# scanner.net
KiCad netlist of a schematic drawn in EAGLE
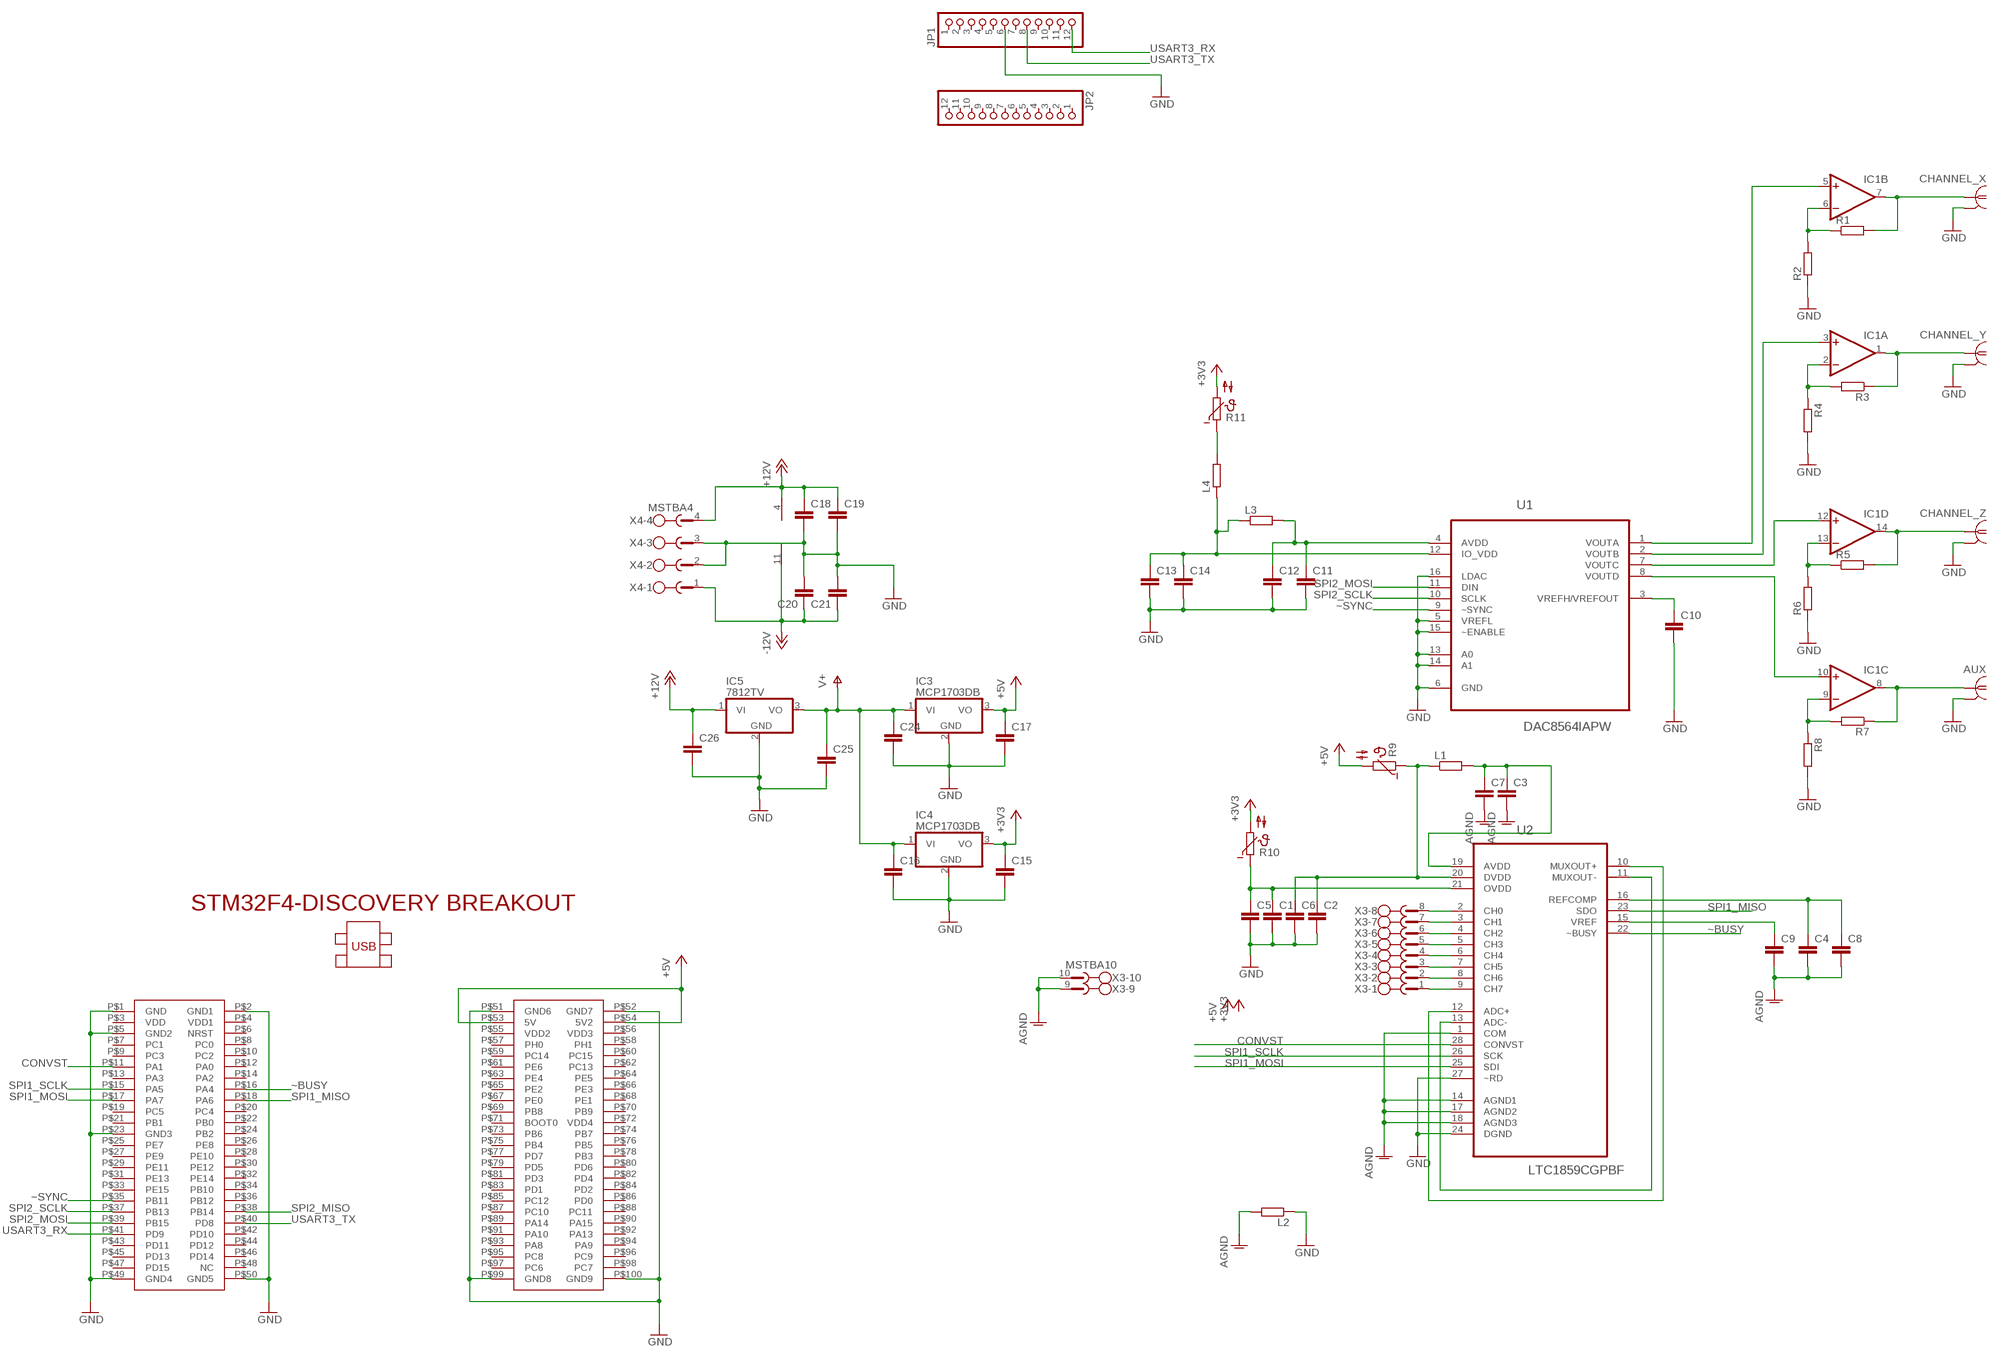
[diagram p0: schematic, sheet 1]

(export (version "E")
  (design (tool "Eeschema 10.0.6"))
  (components
    (comp (ref "AUX")
      (value "1-227161-0")
      (footprint "eagle-import:AMP_227161")
      (fields (field (name "MF") "TYCO ELECTRONICS") (field (name "MPN") "1-227161"))
      (libsource (lib "eagle-import") (part "?2271611--0"))
    )
    (comp (ref "C1")
      (value "C-EUC0805")
      (footprint "eagle-import:C0805")
      (libsource (lib "eagle-import") (part "C-EUC0805"))
    )
    (comp (ref "C2")
      (value "C-EUC0805")
      (footprint "eagle-import:C0805")
      (libsource (lib "eagle-import") (part "C-EUC0805"))
    )
    (comp (ref "C3")
      (value "C-EUC0805")
      (footprint "eagle-import:C0805")
      (libsource (lib "eagle-import") (part "C-EUC0805"))
    )
    (comp (ref "C4")
      (value "C-EUC0805")
      (footprint "eagle-import:C0805")
      (libsource (lib "eagle-import") (part "C-EUC0805"))
    )
    (comp (ref "C5")
      (value "C-EUC1206")
      (footprint "eagle-import:C1206")
      (libsource (lib "eagle-import") (part "C-EUC1206"))
    )
    (comp (ref "C6")
      (value "C-EUC1206")
      (footprint "eagle-import:C1206")
      (libsource (lib "eagle-import") (part "C-EUC1206"))
    )
    (comp (ref "C7")
      (value "C-EUC1206")
      (footprint "eagle-import:C1206")
      (libsource (lib "eagle-import") (part "C-EUC1206"))
    )
    (comp (ref "C8")
      (value "C-EUC1206")
      (footprint "eagle-import:C1206")
      (libsource (lib "eagle-import") (part "C-EUC1206"))
    )
    (comp (ref "C9")
      (value "C-EUC1206")
      (footprint "eagle-import:C1206")
      (libsource (lib "eagle-import") (part "C-EUC1206"))
    )
    (comp (ref "C10")
      (value "C-EUC0805")
      (footprint "eagle-import:C0805")
      (libsource (lib "eagle-import") (part "C-EUC0805"))
    )
    (comp (ref "C11")
      (value "C-EUC0805")
      (footprint "eagle-import:C0805")
      (libsource (lib "eagle-import") (part "C-EUC0805"))
    )
    (comp (ref "C12")
      (value "C-EUC1206")
      (footprint "eagle-import:C1206")
      (libsource (lib "eagle-import") (part "C-EUC1206"))
    )
    (comp (ref "C13")
      (value "C-EUC1206")
      (footprint "eagle-import:C1206")
      (libsource (lib "eagle-import") (part "C-EUC1206"))
    )
    (comp (ref "C14")
      (value "C-EUC0805")
      (footprint "eagle-import:C0805")
      (libsource (lib "eagle-import") (part "C-EUC0805"))
    )
    (comp (ref "C15")
      (value "C-EUC0805")
      (footprint "eagle-import:C0805")
      (libsource (lib "eagle-import") (part "C-EUC0805"))
    )
    (comp (ref "C16")
      (value "C-EUC0805")
      (footprint "eagle-import:C0805")
      (libsource (lib "eagle-import") (part "C-EUC0805"))
    )
    (comp (ref "C17")
      (value "C-EUC0805")
      (footprint "eagle-import:C0805")
      (libsource (lib "eagle-import") (part "C-EUC0805"))
    )
    (comp (ref "C18")
      (value "C-EUC1206")
      (footprint "eagle-import:C1206")
      (libsource (lib "eagle-import") (part "C-EUC1206"))
    )
    (comp (ref "C19")
      (value "C-EUC0805")
      (footprint "eagle-import:C0805")
      (libsource (lib "eagle-import") (part "C-EUC0805"))
    )
    (comp (ref "C20")
      (value "C-EUC1206")
      (footprint "eagle-import:C1206")
      (libsource (lib "eagle-import") (part "C-EUC1206"))
    )
    (comp (ref "C21")
      (value "C-EUC0805")
      (footprint "eagle-import:C0805")
      (libsource (lib "eagle-import") (part "C-EUC0805"))
    )
    (comp (ref "C24")
      (value "C-EUC0805")
      (footprint "eagle-import:C0805")
      (libsource (lib "eagle-import") (part "C-EUC0805"))
    )
    (comp (ref "C25")
      (value "C-EUC1206")
      (footprint "eagle-import:C1206")
      (libsource (lib "eagle-import") (part "C-EUC1206"))
    )
    (comp (ref "C26")
      (value "C-EUC1206")
      (footprint "eagle-import:C1206")
      (libsource (lib "eagle-import") (part "C-EUC1206"))
    )
    (comp (ref "CHANNEL_X")
      (value "1-227161-0")
      (footprint "eagle-import:AMP_227161")
      (fields (field (name "MF") "TYCO ELECTRONICS") (field (name "MPN") "1-227161"))
      (libsource (lib "eagle-import") (part "?2271611--0"))
    )
    (comp (ref "CHANNEL_Y")
      (value "1-227161-0")
      (footprint "eagle-import:AMP_227161")
      (fields (field (name "MF") "TYCO ELECTRONICS") (field (name "MPN") "1-227161"))
      (libsource (lib "eagle-import") (part "?2271611--0"))
    )
    (comp (ref "CHANNEL_Z")
      (value "1-227161-0")
      (footprint "eagle-import:AMP_227161")
      (fields (field (name "MF") "TYCO ELECTRONICS") (field (name "MPN") "1-227161"))
      (libsource (lib "eagle-import") (part "?2271611--0"))
    )
    (comp (ref "IC1")
      (value "4AMP_P4+11D")
      (footprint "eagle-import:SO14")
      (libsource (lib "eagle-import") (part "4AMP_P4+11D"))
    )
    (comp (ref "IC3")
      (value "MCP1703DB")
      (footprint "eagle-import:SOT223")
      (libsource (lib "eagle-import") (part "MCP1703DB"))
    )
    (comp (ref "IC4")
      (value "MCP1703DB")
      (footprint "eagle-import:SOT223")
      (libsource (lib "eagle-import") (part "MCP1703DB"))
    )
    (comp (ref "IC5")
      (value "7812TV")
      (footprint "eagle-import:TO220V")
      (libsource (lib "eagle-import") (part "78TV12"))
    )
    (comp (ref "JP1")
      (value "PINHD-1X12")
      (footprint "eagle-import:1X12")
      (libsource (lib "eagle-import") (part "PINHD-1X12"))
    )
    (comp (ref "JP2")
      (value "PINHD-1X12")
      (footprint "eagle-import:1X12")
      (libsource (lib "eagle-import") (part "PINHD-1X12"))
    )
    (comp (ref "L1")
      (value "R-EU_M1206")
      (footprint "eagle-import:M1206")
      (libsource (lib "eagle-import") (part "R-EU_M1206"))
    )
    (comp (ref "L2")
      (value "R-EU_M1206")
      (footprint "eagle-import:M1206")
      (libsource (lib "eagle-import") (part "R-EU_M1206"))
    )
    (comp (ref "L3")
      (value "R-EU_M1206")
      (footprint "eagle-import:M1206")
      (libsource (lib "eagle-import") (part "R-EU_M1206"))
    )
    (comp (ref "L4")
      (value "R-EU_M1206")
      (footprint "eagle-import:M1206")
      (libsource (lib "eagle-import") (part "R-EU_M1206"))
    )
    (comp (ref "R1")
      (value "R-EU_M0805")
      (footprint "eagle-import:M0805")
      (libsource (lib "eagle-import") (part "R-EU_M0805"))
    )
    (comp (ref "R2")
      (value "R-EU_M0805")
      (footprint "eagle-import:M0805")
      (libsource (lib "eagle-import") (part "R-EU_M0805"))
    )
    (comp (ref "R3")
      (value "R-EU_M0805")
      (footprint "eagle-import:M0805")
      (libsource (lib "eagle-import") (part "R-EU_M0805"))
    )
    (comp (ref "R4")
      (value "R-EU_M0805")
      (footprint "eagle-import:M0805")
      (libsource (lib "eagle-import") (part "R-EU_M0805"))
    )
    (comp (ref "R5")
      (value "R-EU_M0805")
      (footprint "eagle-import:M0805")
      (libsource (lib "eagle-import") (part "R-EU_M0805"))
    )
    (comp (ref "R6")
      (value "R-EU_M0805")
      (footprint "eagle-import:M0805")
      (libsource (lib "eagle-import") (part "R-EU_M0805"))
    )
    (comp (ref "R7")
      (value "R-EU_M0805")
      (footprint "eagle-import:M0805")
      (libsource (lib "eagle-import") (part "R-EU_M0805"))
    )
    (comp (ref "R8")
      (value "R-EU_M0805")
      (footprint "eagle-import:M0805")
      (libsource (lib "eagle-import") (part "R-EU_M0805"))
    )
    (comp (ref "R9")
      (value "NTC644C")
      (footprint "eagle-import:N644C")
      (libsource (lib "eagle-import") (part "NTC644C"))
    )
    (comp (ref "R10")
      (value "NTC644C")
      (footprint "eagle-import:N644C")
      (libsource (lib "eagle-import") (part "NTC644C"))
    )
    (comp (ref "R11")
      (value "NTC644C")
      (footprint "eagle-import:N644C")
      (libsource (lib "eagle-import") (part "NTC644C"))
    )
    (comp (ref "U$2")
      (value "STM32F4-DISCOVERY")
      (footprint "eagle-import:STM32F4-DISCOVERY")
      (libsource (lib "eagle-import") (part "STM32F4-DISCOVERY"))
    )
    (comp (ref "U1")
      (value "DAC8564IAPW")
      (footprint "eagle-import:SOP65P640X120-16N")
      (libsource (lib "eagle-import") (part "DAC8564IAPW"))
    )
    (comp (ref "U2")
      (value "LTC1859CGPBF")
      (footprint "eagle-import:SOP65P780X200-28N")
      (fields (field (name "MPN") "LTC1859CG#PBF"))
      (libsource (lib "eagle-import") (part "LTC1859CGPBF"))
    )
    (comp (ref "X3")
      (value "MSTBA10")
      (footprint "eagle-import:MSTBA10")
      (fields (field (name "MF") "FARNELL") (field (name "MPN") "1757323"))
      (libsource (lib "eagle-import") (part "MSTBA10"))
    )
    (comp (ref "X4")
      (value "MSTBA4")
      (footprint "eagle-import:MSTBA4")
      (fields (field (name "MF") "FARNELL") (field (name "MPN") "1757268"))
      (libsource (lib "eagle-import") (part "MSTBA4"))
    )
  )
  (nets
    (net (code "1") (name "+3V3") (class "Default")
      (node (ref "C15") (pin "1") (pinfunction "1_1") (pintype "passive"))
      (node (ref "IC4") (pin "3") (pinfunction "VO_3") (pintype "passive"))
      (node (ref "R10") (pin "2") (pinfunction "2_2") (pintype "passive"))
      (node (ref "R11") (pin "2") (pinfunction "2_2") (pintype "passive"))
    )
    (net (code "2") (name "+5V") (class "Default")
      (node (ref "C17") (pin "1") (pinfunction "1_1") (pintype "passive"))
      (node (ref "IC3") (pin "3") (pinfunction "VO_3") (pintype "passive"))
      (node (ref "R9") (pin "2") (pinfunction "2_2") (pintype "passive"))
      (node (ref "U$2") (pin "P$53") (pinfunction "5V_P$53") (pintype "bidirectional"))
      (node (ref "U$2") (pin "P$54") (pinfunction "5V2_P$54") (pintype "bidirectional"))
    )
    (net (code "3") (name "+12V") (class "Default")
      (node (ref "C18") (pin "1") (pinfunction "1_1") (pintype "passive"))
      (node (ref "C19") (pin "1") (pinfunction "1_1") (pintype "passive"))
      (node (ref "C26") (pin "1") (pinfunction "1_1") (pintype "passive"))
      (node (ref "IC1") (pin "4") (pinfunction "V+_4") (pintype "power_in"))
      (node (ref "IC5") (pin "1") (pinfunction "VI_1") (pintype "input"))
      (node (ref "X4") (pin "4") (pinfunction "1_4") (pintype "passive"))
    )
    (net (code "4") (name "-12V") (class "Default")
      (node (ref "C20") (pin "1") (pinfunction "1_1") (pintype "passive"))
      (node (ref "C21") (pin "1") (pinfunction "1_1") (pintype "passive"))
      (node (ref "IC1") (pin "11") (pinfunction "V-_11") (pintype "power_in"))
      (node (ref "X4") (pin "1") (pinfunction "1_1") (pintype "passive"))
    )
    (net (code "5") (name "/CONVST") (class "Default")
      (node (ref "U$2") (pin "P$11") (pinfunction "PA1_P$11") (pintype "bidirectional"))
      (node (ref "U2") (pin "28") (pinfunction "CONVST_28") (pintype "input"))
    )
    (net (code "6") (name "/SPI1_MISO") (class "Default")
      (node (ref "U$2") (pin "P$18") (pinfunction "PA6_P$18") (pintype "bidirectional"))
      (node (ref "U2") (pin "23") (pinfunction "SDO_23") (pintype "output"))
    )
    (net (code "7") (name "/SPI1_MOSI") (class "Default")
      (node (ref "U$2") (pin "P$17") (pinfunction "PA7_P$17") (pintype "bidirectional"))
      (node (ref "U2") (pin "25") (pinfunction "SDI_25") (pintype "input"))
    )
    (net (code "8") (name "/SPI1_SCLK") (class "Default")
      (node (ref "U$2") (pin "P$15") (pinfunction "PA5_P$15") (pintype "bidirectional"))
      (node (ref "U2") (pin "26") (pinfunction "SCK_26") (pintype "input"))
    )
    (net (code "9") (name "/SPI2_MISO") (class "Default")
      (node (ref "U$2") (pin "P$38") (pinfunction "PB14_P$38") (pintype "bidirectional"))
    )
    (net (code "10") (name "/SPI2_MOSI") (class "Default")
      (node (ref "U$2") (pin "P$39") (pinfunction "PB15_P$39") (pintype "bidirectional"))
      (node (ref "U1") (pin "11") (pinfunction "DIN_11") (pintype "input"))
    )
    (net (code "11") (name "/SPI2_SCLK") (class "Default")
      (node (ref "U$2") (pin "P$37") (pinfunction "PB13_P$37") (pintype "bidirectional"))
      (node (ref "U1") (pin "10") (pinfunction "SCLK_10") (pintype "input"))
    )
    (net (code "12") (name "/USART3_RX") (class "Default")
      (node (ref "JP1") (pin "12") (pinfunction "12_12") (pintype "passive"))
      (node (ref "U$2") (pin "P$41") (pinfunction "PD9_P$41") (pintype "bidirectional"))
    )
    (net (code "13") (name "/USART3_TX") (class "Default")
      (node (ref "JP1") (pin "8") (pinfunction "8_8") (pintype "passive"))
      (node (ref "U$2") (pin "P$40") (pinfunction "PD8_P$40") (pintype "bidirectional"))
    )
    (net (code "14") (name "/~{BUSY}") (class "Default")
      (node (ref "U$2") (pin "P$16") (pinfunction "PA4_P$16") (pintype "bidirectional"))
      (node (ref "U2") (pin "22") (pinfunction "~{BUSY}_22") (pintype "output"))
    )
    (net (code "15") (name "/~{SYNC}") (class "Default")
      (node (ref "U$2") (pin "P$35") (pinfunction "PB11_P$35") (pintype "bidirectional"))
      (node (ref "U1") (pin "9") (pinfunction "~{SYNC}_9") (pintype "input"))
    )
    (net (code "16") (name "AGND") (class "Default")
      (node (ref "C3") (pin "2") (pinfunction "2_2") (pintype "passive"))
      (node (ref "C4") (pin "2") (pinfunction "2_2") (pintype "passive"))
      (node (ref "C7") (pin "2") (pinfunction "2_2") (pintype "passive"))
      (node (ref "C8") (pin "2") (pinfunction "2_2") (pintype "passive"))
      (node (ref "C9") (pin "2") (pinfunction "2_2") (pintype "passive"))
      (node (ref "L2") (pin "2") (pinfunction "2_2") (pintype "passive"))
      (node (ref "U2") (pin "1") (pinfunction "COM_1") (pintype "input"))
      (node (ref "U2") (pin "14") (pinfunction "AGND1_14") (pintype "passive"))
      (node (ref "U2") (pin "17") (pinfunction "AGND2_17") (pintype "passive"))
      (node (ref "U2") (pin "18") (pinfunction "AGND3_18") (pintype "passive"))
      (node (ref "X3") (pin "10") (pinfunction "1_10") (pintype "passive"))
      (node (ref "X3") (pin "9") (pinfunction "1_9") (pintype "passive"))
    )
    (net (code "17") (name "GND") (class "Default")
      (node (ref "AUX") (pin "2") (pinfunction "2_2") (pintype "passive"))
      (node (ref "C1") (pin "2") (pinfunction "2_2") (pintype "passive"))
      (node (ref "C10") (pin "2") (pinfunction "2_2") (pintype "passive"))
      (node (ref "C11") (pin "2") (pinfunction "2_2") (pintype "passive"))
      (node (ref "C12") (pin "2") (pinfunction "2_2") (pintype "passive"))
      (node (ref "C13") (pin "2") (pinfunction "2_2") (pintype "passive"))
      (node (ref "C14") (pin "2") (pinfunction "2_2") (pintype "passive"))
      (node (ref "C15") (pin "2") (pinfunction "2_2") (pintype "passive"))
      (node (ref "C16") (pin "2") (pinfunction "2_2") (pintype "passive"))
      (node (ref "C17") (pin "2") (pinfunction "2_2") (pintype "passive"))
      (node (ref "C18") (pin "2") (pinfunction "2_2") (pintype "passive"))
      (node (ref "C19") (pin "2") (pinfunction "2_2") (pintype "passive"))
      (node (ref "C2") (pin "2") (pinfunction "2_2") (pintype "passive"))
      (node (ref "C20") (pin "2") (pinfunction "2_2") (pintype "passive"))
      (node (ref "C21") (pin "2") (pinfunction "2_2") (pintype "passive"))
      (node (ref "C24") (pin "2") (pinfunction "2_2") (pintype "passive"))
      (node (ref "C25") (pin "2") (pinfunction "2_2") (pintype "passive"))
      (node (ref "C26") (pin "2") (pinfunction "2_2") (pintype "passive"))
      (node (ref "C5") (pin "2") (pinfunction "2_2") (pintype "passive"))
      (node (ref "C6") (pin "2") (pinfunction "2_2") (pintype "passive"))
      (node (ref "CHANNEL_X") (pin "2") (pinfunction "2_2") (pintype "passive"))
      (node (ref "CHANNEL_Y") (pin "2") (pinfunction "2_2") (pintype "passive"))
      (node (ref "CHANNEL_Z") (pin "2") (pinfunction "2_2") (pintype "passive"))
      (node (ref "IC3") (pin "2") (pinfunction "GND_2") (pintype "passive"))
      (node (ref "IC4") (pin "2") (pinfunction "GND_2") (pintype "passive"))
      (node (ref "IC5") (pin "2") (pinfunction "GND_2") (pintype "passive"))
      (node (ref "JP1") (pin "6") (pinfunction "6_6") (pintype "passive"))
      (node (ref "L2") (pin "1") (pinfunction "1_1") (pintype "passive"))
      (node (ref "R2") (pin "1") (pinfunction "1_1") (pintype "passive"))
      (node (ref "R4") (pin "2") (pinfunction "2_2") (pintype "passive"))
      (node (ref "R6") (pin "1") (pinfunction "1_1") (pintype "passive"))
      (node (ref "R8") (pin "2") (pinfunction "2_2") (pintype "passive"))
      (node (ref "U$2") (pin "P$1") (pinfunction "GND_P$1") (pintype "bidirectional"))
      (node (ref "U$2") (pin "P$100") (pinfunction "GND9_P$100") (pintype "bidirectional"))
      (node (ref "U$2") (pin "P$2") (pinfunction "GND1_P$2") (pintype "bidirectional"))
      (node (ref "U$2") (pin "P$23") (pinfunction "GND3_P$23") (pintype "bidirectional"))
      (node (ref "U$2") (pin "P$49") (pinfunction "GND4_P$49") (pintype "bidirectional"))
      (node (ref "U$2") (pin "P$5") (pinfunction "GND2_P$5") (pintype "bidirectional"))
      (node (ref "U$2") (pin "P$50") (pinfunction "GND5_P$50") (pintype "bidirectional"))
      (node (ref "U$2") (pin "P$51") (pinfunction "GND6_P$51") (pintype "bidirectional"))
      (node (ref "U$2") (pin "P$52") (pinfunction "GND7_P$52") (pintype "bidirectional"))
      (node (ref "U$2") (pin "P$99") (pinfunction "GND8_P$99") (pintype "bidirectional"))
      (node (ref "U1") (pin "13") (pinfunction "A0_13") (pintype "input"))
      (node (ref "U1") (pin "14") (pinfunction "A1_14") (pintype "input"))
      (node (ref "U1") (pin "15") (pinfunction "~{ENABLE}_15") (pintype "input"))
      (node (ref "U1") (pin "16") (pinfunction "LDAC_16") (pintype "input"))
      (node (ref "U1") (pin "5") (pinfunction "VREFL_5") (pintype "input"))
      (node (ref "U1") (pin "6") (pinfunction "GND_6") (pintype "passive"))
      (node (ref "U2") (pin "24") (pinfunction "DGND_24") (pintype "passive"))
      (node (ref "U2") (pin "27") (pinfunction "~{RD}_27") (pintype "input"))
      (node (ref "X4") (pin "2") (pinfunction "1_2") (pintype "passive"))
      (node (ref "X4") (pin "3") (pinfunction "1_3") (pintype "passive"))
    )
    (net (code "18") (name "Net-(IC1A-+IN)") (class "Default")
      (node (ref "IC1") (pin "3") (pinfunction "+IN_3") (pintype "input"))
      (node (ref "U1") (pin "2") (pinfunction "VOUTB_2") (pintype "output"))
    )
    (net (code "19") (name "Net-(IC1A--IN)") (class "Default")
      (node (ref "IC1") (pin "2") (pinfunction "-IN_2") (pintype "input"))
      (node (ref "R3") (pin "2") (pinfunction "2_2") (pintype "passive"))
      (node (ref "R4") (pin "1") (pinfunction "1_1") (pintype "passive"))
    )
    (net (code "20") (name "Net-(IC1A-OUT)") (class "Default")
      (node (ref "CHANNEL_Y") (pin "1") (pinfunction "1_1") (pintype "passive"))
      (node (ref "IC1") (pin "1") (pinfunction "OUT_1") (pintype "output"))
      (node (ref "R3") (pin "1") (pinfunction "1_1") (pintype "passive"))
    )
    (net (code "21") (name "Net-(IC1B-+IN)") (class "Default")
      (node (ref "IC1") (pin "5") (pinfunction "+IN_5") (pintype "input"))
      (node (ref "U1") (pin "1") (pinfunction "VOUTA_1") (pintype "output"))
    )
    (net (code "22") (name "Net-(IC1B--IN)") (class "Default")
      (node (ref "IC1") (pin "6") (pinfunction "-IN_6") (pintype "input"))
      (node (ref "R1") (pin "1") (pinfunction "1_1") (pintype "passive"))
      (node (ref "R2") (pin "2") (pinfunction "2_2") (pintype "passive"))
    )
    (net (code "23") (name "Net-(IC1B-OUT)") (class "Default")
      (node (ref "CHANNEL_X") (pin "1") (pinfunction "1_1") (pintype "passive"))
      (node (ref "IC1") (pin "7") (pinfunction "OUT_7") (pintype "output"))
      (node (ref "R1") (pin "2") (pinfunction "2_2") (pintype "passive"))
    )
    (net (code "24") (name "Net-(IC1C-+IN)") (class "Default")
      (node (ref "IC1") (pin "10") (pinfunction "+IN_10") (pintype "input"))
      (node (ref "U1") (pin "8") (pinfunction "VOUTD_8") (pintype "output"))
    )
    (net (code "25") (name "Net-(IC1C--IN)") (class "Default")
      (node (ref "IC1") (pin "9") (pinfunction "-IN_9") (pintype "input"))
      (node (ref "R7") (pin "2") (pinfunction "2_2") (pintype "passive"))
      (node (ref "R8") (pin "1") (pinfunction "1_1") (pintype "passive"))
    )
    (net (code "26") (name "Net-(IC1C-OUT)") (class "Default")
      (node (ref "AUX") (pin "1") (pinfunction "1_1") (pintype "passive"))
      (node (ref "IC1") (pin "8") (pinfunction "OUT_8") (pintype "output"))
      (node (ref "R7") (pin "1") (pinfunction "1_1") (pintype "passive"))
    )
    (net (code "27") (name "Net-(IC1D-+IN)") (class "Default")
      (node (ref "IC1") (pin "12") (pinfunction "+IN_12") (pintype "input"))
      (node (ref "U1") (pin "7") (pinfunction "VOUTC_7") (pintype "output"))
    )
    (net (code "28") (name "Net-(IC1D--IN)") (class "Default")
      (node (ref "IC1") (pin "13") (pinfunction "-IN_13") (pintype "input"))
      (node (ref "R5") (pin "1") (pinfunction "1_1") (pintype "passive"))
      (node (ref "R6") (pin "2") (pinfunction "2_2") (pintype "passive"))
    )
    (net (code "29") (name "Net-(IC1D-OUT)") (class "Default")
      (node (ref "CHANNEL_Z") (pin "1") (pinfunction "1_1") (pintype "passive"))
      (node (ref "IC1") (pin "14") (pinfunction "OUT_14") (pintype "output"))
      (node (ref "R5") (pin "2") (pinfunction "2_2") (pintype "passive"))
    )
    (net (code "30") (name "Net-(L4-Pad2)") (class "Default")
      (node (ref "L4") (pin "2") (pinfunction "2_2") (pintype "passive"))
      (node (ref "R11") (pin "1") (pinfunction "1_1") (pintype "passive"))
    )
    (net (code "31") (name "Net-(U1-AVDD)") (class "Default")
      (node (ref "C11") (pin "1") (pinfunction "1_1") (pintype "passive"))
      (node (ref "C12") (pin "1") (pinfunction "1_1") (pintype "passive"))
      (node (ref "L3") (pin "2") (pinfunction "2_2") (pintype "passive"))
      (node (ref "U1") (pin "4") (pinfunction "AVDD_4") (pintype "power_in"))
    )
    (net (code "32") (name "Net-(U1-IO_VDD)") (class "Default")
      (node (ref "C13") (pin "1") (pinfunction "1_1") (pintype "passive"))
      (node (ref "C14") (pin "1") (pinfunction "1_1") (pintype "passive"))
      (node (ref "L3") (pin "1") (pinfunction "1_1") (pintype "passive"))
      (node (ref "L4") (pin "1") (pinfunction "1_1") (pintype "passive"))
      (node (ref "U1") (pin "12") (pinfunction "IO_VDD_12") (pintype "power_in"))
    )
    (net (code "33") (name "Net-(U1-VREFH{slash}VREFOUT)") (class "Default")
      (node (ref "C10") (pin "1") (pinfunction "1_1") (pintype "passive"))
      (node (ref "U1") (pin "3") (pinfunction "VREFH/VREFOUT_3") (pintype "bidirectional"))
    )
    (net (code "34") (name "Net-(U2-ADC+)") (class "Default")
      (node (ref "U2") (pin "10") (pinfunction "MUXOUT+_10") (pintype "output"))
      (node (ref "U2") (pin "12") (pinfunction "ADC+_12") (pintype "input"))
    )
    (net (code "35") (name "Net-(U2-ADC-)") (class "Default")
      (node (ref "U2") (pin "11") (pinfunction "MUXOUT-_11") (pintype "output"))
      (node (ref "U2") (pin "13") (pinfunction "ADC-_13") (pintype "input"))
    )
    (net (code "36") (name "Net-(U2-AVDD)") (class "Default")
      (node (ref "C3") (pin "1") (pinfunction "1_1") (pintype "passive"))
      (node (ref "C7") (pin "1") (pinfunction "1_1") (pintype "passive"))
      (node (ref "L1") (pin "2") (pinfunction "2_2") (pintype "passive"))
      (node (ref "U2") (pin "19") (pinfunction "AVDD_19") (pintype "power_in"))
    )
    (net (code "37") (name "Net-(U2-CH0)") (class "Default")
      (node (ref "U2") (pin "2") (pinfunction "CH0_2") (pintype "input"))
      (node (ref "X3") (pin "8") (pinfunction "1_8") (pintype "passive"))
    )
    (net (code "38") (name "Net-(U2-CH1)") (class "Default")
      (node (ref "U2") (pin "3") (pinfunction "CH1_3") (pintype "input"))
      (node (ref "X3") (pin "7") (pinfunction "1_7") (pintype "passive"))
    )
    (net (code "39") (name "Net-(U2-CH2)") (class "Default")
      (node (ref "U2") (pin "4") (pinfunction "CH2_4") (pintype "input"))
      (node (ref "X3") (pin "6") (pinfunction "1_6") (pintype "passive"))
    )
    (net (code "40") (name "Net-(U2-CH3)") (class "Default")
      (node (ref "U2") (pin "5") (pinfunction "CH3_5") (pintype "input"))
      (node (ref "X3") (pin "5") (pinfunction "1_5") (pintype "passive"))
    )
    (net (code "41") (name "Net-(U2-CH4)") (class "Default")
      (node (ref "U2") (pin "6") (pinfunction "CH4_6") (pintype "input"))
      (node (ref "X3") (pin "4") (pinfunction "1_4") (pintype "passive"))
    )
    (net (code "42") (name "Net-(U2-CH5)") (class "Default")
      (node (ref "U2") (pin "7") (pinfunction "CH5_7") (pintype "input"))
      (node (ref "X3") (pin "3") (pinfunction "1_3") (pintype "passive"))
    )
    (net (code "43") (name "Net-(U2-CH6)") (class "Default")
      (node (ref "U2") (pin "8") (pinfunction "CH6_8") (pintype "input"))
      (node (ref "X3") (pin "2") (pinfunction "1_2") (pintype "passive"))
    )
    (net (code "44") (name "Net-(U2-CH7)") (class "Default")
      (node (ref "U2") (pin "9") (pinfunction "CH7_9") (pintype "input"))
      (node (ref "X3") (pin "1") (pinfunction "1_1") (pintype "passive"))
    )
    (net (code "45") (name "Net-(U2-DVDD)") (class "Default")
      (node (ref "C2") (pin "1") (pinfunction "1_1") (pintype "passive"))
      (node (ref "C6") (pin "1") (pinfunction "1_1") (pintype "passive"))
      (node (ref "L1") (pin "1") (pinfunction "1_1") (pintype "passive"))
      (node (ref "R9") (pin "1") (pinfunction "1_1") (pintype "passive"))
      (node (ref "U2") (pin "20") (pinfunction "DVDD_20") (pintype "power_in"))
    )
    (net (code "46") (name "Net-(U2-OVDD)") (class "Default")
      (node (ref "C1") (pin "1") (pinfunction "1_1") (pintype "passive"))
      (node (ref "C5") (pin "1") (pinfunction "1_1") (pintype "passive"))
      (node (ref "R10") (pin "1") (pinfunction "1_1") (pintype "passive"))
      (node (ref "U2") (pin "21") (pinfunction "OVDD_21") (pintype "power_in"))
    )
    (net (code "47") (name "Net-(U2-REFCOMP)") (class "Default")
      (node (ref "C4") (pin "1") (pinfunction "1_1") (pintype "passive"))
      (node (ref "C8") (pin "1") (pinfunction "1_1") (pintype "passive"))
      (node (ref "U2") (pin "16") (pinfunction "REFCOMP_16") (pintype "output"))
    )
    (net (code "48") (name "Net-(U2-VREF)") (class "Default")
      (node (ref "C9") (pin "1") (pinfunction "1_1") (pintype "passive"))
      (node (ref "U2") (pin "15") (pinfunction "VREF_15") (pintype "output"))
    )
    (net (code "49") (name "V+") (class "Default")
      (node (ref "C16") (pin "1") (pinfunction "1_1") (pintype "passive"))
      (node (ref "C24") (pin "1") (pinfunction "1_1") (pintype "passive"))
      (node (ref "C25") (pin "1") (pinfunction "1_1") (pintype "passive"))
      (node (ref "IC3") (pin "1") (pinfunction "VI_1") (pintype "input"))
      (node (ref "IC4") (pin "1") (pinfunction "VI_1") (pintype "input"))
      (node (ref "IC5") (pin "3") (pinfunction "VO_3") (pintype "passive"))
    )
    (net (code "50") (name "unconnected-(JP1-Pad1)") (class "Default")
      (node (ref "JP1") (pin "1") (pinfunction "1_1") (pintype "passive"))
    )
    (net (code "51") (name "unconnected-(JP1-Pad2)") (class "Default")
      (node (ref "JP1") (pin "2") (pinfunction "2_2") (pintype "passive"))
    )
    (net (code "52") (name "unconnected-(JP1-Pad3)") (class "Default")
      (node (ref "JP1") (pin "3") (pinfunction "3_3") (pintype "passive"))
    )
    (net (code "53") (name "unconnected-(JP1-Pad4)") (class "Default")
      (node (ref "JP1") (pin "4") (pinfunction "4_4") (pintype "passive"))
    )
    (net (code "54") (name "unconnected-(JP1-Pad5)") (class "Default")
      (node (ref "JP1") (pin "5") (pinfunction "5_5") (pintype "passive"))
    )
    (net (code "55") (name "unconnected-(JP1-Pad7)") (class "Default")
      (node (ref "JP1") (pin "7") (pinfunction "7_7") (pintype "passive"))
    )
    (net (code "56") (name "unconnected-(JP1-Pad9)") (class "Default")
      (node (ref "JP1") (pin "9") (pinfunction "9_9") (pintype "passive"))
    )
    (net (code "57") (name "unconnected-(JP1-Pad10)") (class "Default")
      (node (ref "JP1") (pin "10") (pinfunction "10_10") (pintype "passive"))
    )
    (net (code "58") (name "unconnected-(JP1-Pad11)") (class "Default")
      (node (ref "JP1") (pin "11") (pinfunction "11_11") (pintype "passive"))
    )
    (net (code "59") (name "unconnected-(JP2-Pad1)") (class "Default")
      (node (ref "JP2") (pin "1") (pinfunction "1_1") (pintype "passive"))
    )
    (net (code "60") (name "unconnected-(JP2-Pad2)") (class "Default")
      (node (ref "JP2") (pin "2") (pinfunction "2_2") (pintype "passive"))
    )
    (net (code "61") (name "unconnected-(JP2-Pad3)") (class "Default")
      (node (ref "JP2") (pin "3") (pinfunction "3_3") (pintype "passive"))
    )
    (net (code "62") (name "unconnected-(JP2-Pad4)") (class "Default")
      (node (ref "JP2") (pin "4") (pinfunction "4_4") (pintype "passive"))
    )
    (net (code "63") (name "unconnected-(JP2-Pad5)") (class "Default")
      (node (ref "JP2") (pin "5") (pinfunction "5_5") (pintype "passive"))
    )
    (net (code "64") (name "unconnected-(JP2-Pad6)") (class "Default")
      (node (ref "JP2") (pin "6") (pinfunction "6_6") (pintype "passive"))
    )
    (net (code "65") (name "unconnected-(JP2-Pad7)") (class "Default")
      (node (ref "JP2") (pin "7") (pinfunction "7_7") (pintype "passive"))
    )
    (net (code "66") (name "unconnected-(JP2-Pad8)") (class "Default")
      (node (ref "JP2") (pin "8") (pinfunction "8_8") (pintype "passive"))
    )
    (net (code "67") (name "unconnected-(JP2-Pad9)") (class "Default")
      (node (ref "JP2") (pin "9") (pinfunction "9_9") (pintype "passive"))
    )
    (net (code "68") (name "unconnected-(JP2-Pad10)") (class "Default")
      (node (ref "JP2") (pin "10") (pinfunction "10_10") (pintype "passive"))
    )
    (net (code "69") (name "unconnected-(JP2-Pad11)") (class "Default")
      (node (ref "JP2") (pin "11") (pinfunction "11_11") (pintype "passive"))
    )
    (net (code "70") (name "unconnected-(JP2-Pad12)") (class "Default")
      (node (ref "JP2") (pin "12") (pinfunction "12_12") (pintype "passive"))
    )
    (net (code "71") (name "unconnected-(U$2-BOOT0-PadP$71)") (class "Default")
      (node (ref "U$2") (pin "P$71") (pinfunction "BOOT0_P$71") (pintype "bidirectional"))
    )
    (net (code "72") (name "unconnected-(U$2-NC-PadP$48)") (class "Default")
      (node (ref "U$2") (pin "P$48") (pinfunction "NC_P$48") (pintype "bidirectional"))
    )
    (net (code "73") (name "unconnected-(U$2-NRST-PadP$6)") (class "Default")
      (node (ref "U$2") (pin "P$6") (pinfunction "NRST_P$6") (pintype "bidirectional"))
    )
    (net (code "74") (name "unconnected-(U$2-PA0-PadP$12)") (class "Default")
      (node (ref "U$2") (pin "P$12") (pinfunction "PA0_P$12") (pintype "bidirectional"))
    )
    (net (code "75") (name "unconnected-(U$2-PA2-PadP$14)") (class "Default")
      (node (ref "U$2") (pin "P$14") (pinfunction "PA2_P$14") (pintype "bidirectional"))
    )
    (net (code "76") (name "unconnected-(U$2-PA3-PadP$13)") (class "Default")
      (node (ref "U$2") (pin "P$13") (pinfunction "PA3_P$13") (pintype "bidirectional"))
    )
    (net (code "77") (name "unconnected-(U$2-PA8-PadP$93)") (class "Default")
      (node (ref "U$2") (pin "P$93") (pinfunction "PA8_P$93") (pintype "bidirectional"))
    )
    (net (code "78") (name "unconnected-(U$2-PA9-PadP$94)") (class "Default")
      (node (ref "U$2") (pin "P$94") (pinfunction "PA9_P$94") (pintype "bidirectional"))
    )
    (net (code "79") (name "unconnected-(U$2-PA10-PadP$91)") (class "Default")
      (node (ref "U$2") (pin "P$91") (pinfunction "PA10_P$91") (pintype "bidirectional"))
    )
    (net (code "80") (name "unconnected-(U$2-PA13-PadP$92)") (class "Default")
      (node (ref "U$2") (pin "P$92") (pinfunction "PA13_P$92") (pintype "bidirectional"))
    )
    (net (code "81") (name "unconnected-(U$2-PA14-PadP$89)") (class "Default")
      (node (ref "U$2") (pin "P$89") (pinfunction "PA14_P$89") (pintype "bidirectional"))
    )
    (net (code "82") (name "unconnected-(U$2-PA15-PadP$90)") (class "Default")
      (node (ref "U$2") (pin "P$90") (pinfunction "PA15_P$90") (pintype "bidirectional"))
    )
    (net (code "83") (name "unconnected-(U$2-PB0-PadP$22)") (class "Default")
      (node (ref "U$2") (pin "P$22") (pinfunction "PB0_P$22") (pintype "bidirectional"))
    )
    (net (code "84") (name "unconnected-(U$2-PB1-PadP$21)") (class "Default")
      (node (ref "U$2") (pin "P$21") (pinfunction "PB1_P$21") (pintype "bidirectional"))
    )
    (net (code "85") (name "unconnected-(U$2-PB2-PadP$24)") (class "Default")
      (node (ref "U$2") (pin "P$24") (pinfunction "PB2_P$24") (pintype "bidirectional"))
    )
    (net (code "86") (name "unconnected-(U$2-PB3-PadP$78)") (class "Default")
      (node (ref "U$2") (pin "P$78") (pinfunction "PB3_P$78") (pintype "bidirectional"))
    )
    (net (code "87") (name "unconnected-(U$2-PB4-PadP$75)") (class "Default")
      (node (ref "U$2") (pin "P$75") (pinfunction "PB4_P$75") (pintype "bidirectional"))
    )
    (net (code "88") (name "unconnected-(U$2-PB5-PadP$76)") (class "Default")
      (node (ref "U$2") (pin "P$76") (pinfunction "PB5_P$76") (pintype "bidirectional"))
    )
    (net (code "89") (name "unconnected-(U$2-PB6-PadP$73)") (class "Default")
      (node (ref "U$2") (pin "P$73") (pinfunction "PB6_P$73") (pintype "bidirectional"))
    )
    (net (code "90") (name "unconnected-(U$2-PB7-PadP$74)") (class "Default")
      (node (ref "U$2") (pin "P$74") (pinfunction "PB7_P$74") (pintype "bidirectional"))
    )
    (net (code "91") (name "unconnected-(U$2-PB8-PadP$69)") (class "Default")
      (node (ref "U$2") (pin "P$69") (pinfunction "PB8_P$69") (pintype "bidirectional"))
    )
    (net (code "92") (name "unconnected-(U$2-PB9-PadP$70)") (class "Default")
      (node (ref "U$2") (pin "P$70") (pinfunction "PB9_P$70") (pintype "bidirectional"))
    )
    (net (code "93") (name "unconnected-(U$2-PB10-PadP$34)") (class "Default")
      (node (ref "U$2") (pin "P$34") (pinfunction "PB10_P$34") (pintype "bidirectional"))
    )
    (net (code "94") (name "unconnected-(U$2-PB12-PadP$36)") (class "Default")
      (node (ref "U$2") (pin "P$36") (pinfunction "PB12_P$36") (pintype "bidirectional"))
    )
    (net (code "95") (name "unconnected-(U$2-PC0-PadP$8)") (class "Default")
      (node (ref "U$2") (pin "P$8") (pinfunction "PC0_P$8") (pintype "bidirectional"))
    )
    (net (code "96") (name "unconnected-(U$2-PC1-PadP$7)") (class "Default")
      (node (ref "U$2") (pin "P$7") (pinfunction "PC1_P$7") (pintype "bidirectional"))
    )
    (net (code "97") (name "unconnected-(U$2-PC2-PadP$10)") (class "Default")
      (node (ref "U$2") (pin "P$10") (pinfunction "PC2_P$10") (pintype "bidirectional"))
    )
    (net (code "98") (name "unconnected-(U$2-PC3-PadP$9)") (class "Default")
      (node (ref "U$2") (pin "P$9") (pinfunction "PC3_P$9") (pintype "bidirectional"))
    )
    (net (code "99") (name "unconnected-(U$2-PC4-PadP$20)") (class "Default")
      (node (ref "U$2") (pin "P$20") (pinfunction "PC4_P$20") (pintype "bidirectional"))
    )
    (net (code "100") (name "unconnected-(U$2-PC5-PadP$19)") (class "Default")
      (node (ref "U$2") (pin "P$19") (pinfunction "PC5_P$19") (pintype "bidirectional"))
    )
    (net (code "101") (name "unconnected-(U$2-PC6-PadP$97)") (class "Default")
      (node (ref "U$2") (pin "P$97") (pinfunction "PC6_P$97") (pintype "bidirectional"))
    )
    (net (code "102") (name "unconnected-(U$2-PC7-PadP$98)") (class "Default")
      (node (ref "U$2") (pin "P$98") (pinfunction "PC7_P$98") (pintype "bidirectional"))
    )
    (net (code "103") (name "unconnected-(U$2-PC8-PadP$95)") (class "Default")
      (node (ref "U$2") (pin "P$95") (pinfunction "PC8_P$95") (pintype "bidirectional"))
    )
    (net (code "104") (name "unconnected-(U$2-PC9-PadP$96)") (class "Default")
      (node (ref "U$2") (pin "P$96") (pinfunction "PC9_P$96") (pintype "bidirectional"))
    )
    (net (code "105") (name "unconnected-(U$2-PC10-PadP$87)") (class "Default")
      (node (ref "U$2") (pin "P$87") (pinfunction "PC10_P$87") (pintype "bidirectional"))
    )
    (net (code "106") (name "unconnected-(U$2-PC11-PadP$88)") (class "Default")
      (node (ref "U$2") (pin "P$88") (pinfunction "PC11_P$88") (pintype "bidirectional"))
    )
    (net (code "107") (name "unconnected-(U$2-PC12-PadP$85)") (class "Default")
      (node (ref "U$2") (pin "P$85") (pinfunction "PC12_P$85") (pintype "bidirectional"))
    )
    (net (code "108") (name "unconnected-(U$2-PC13-PadP$62)") (class "Default")
      (node (ref "U$2") (pin "P$62") (pinfunction "PC13_P$62") (pintype "bidirectional"))
    )
    (net (code "109") (name "unconnected-(U$2-PC14-PadP$59)") (class "Default")
      (node (ref "U$2") (pin "P$59") (pinfunction "PC14_P$59") (pintype "bidirectional"))
    )
    (net (code "110") (name "unconnected-(U$2-PC15-PadP$60)") (class "Default")
      (node (ref "U$2") (pin "P$60") (pinfunction "PC15_P$60") (pintype "bidirectional"))
    )
    (net (code "111") (name "unconnected-(U$2-PD0-PadP$86)") (class "Default")
      (node (ref "U$2") (pin "P$86") (pinfunction "PD0_P$86") (pintype "bidirectional"))
    )
    (net (code "112") (name "unconnected-(U$2-PD1-PadP$83)") (class "Default")
      (node (ref "U$2") (pin "P$83") (pinfunction "PD1_P$83") (pintype "bidirectional"))
    )
    (net (code "113") (name "unconnected-(U$2-PD2-PadP$84)") (class "Default")
      (node (ref "U$2") (pin "P$84") (pinfunction "PD2_P$84") (pintype "bidirectional"))
    )
    (net (code "114") (name "unconnected-(U$2-PD3-PadP$81)") (class "Default")
      (node (ref "U$2") (pin "P$81") (pinfunction "PD3_P$81") (pintype "bidirectional"))
    )
    (net (code "115") (name "unconnected-(U$2-PD4-PadP$82)") (class "Default")
      (node (ref "U$2") (pin "P$82") (pinfunction "PD4_P$82") (pintype "bidirectional"))
    )
    (net (code "116") (name "unconnected-(U$2-PD5-PadP$79)") (class "Default")
      (node (ref "U$2") (pin "P$79") (pinfunction "PD5_P$79") (pintype "bidirectional"))
    )
    (net (code "117") (name "unconnected-(U$2-PD6-PadP$80)") (class "Default")
      (node (ref "U$2") (pin "P$80") (pinfunction "PD6_P$80") (pintype "bidirectional"))
    )
    (net (code "118") (name "unconnected-(U$2-PD7-PadP$77)") (class "Default")
      (node (ref "U$2") (pin "P$77") (pinfunction "PD7_P$77") (pintype "bidirectional"))
    )
    (net (code "119") (name "unconnected-(U$2-PD10-PadP$42)") (class "Default")
      (node (ref "U$2") (pin "P$42") (pinfunction "PD10_P$42") (pintype "bidirectional"))
    )
    (net (code "120") (name "unconnected-(U$2-PD11-PadP$43)") (class "Default")
      (node (ref "U$2") (pin "P$43") (pinfunction "PD11_P$43") (pintype "bidirectional"))
    )
    (net (code "121") (name "unconnected-(U$2-PD12-PadP$44)") (class "Default")
      (node (ref "U$2") (pin "P$44") (pinfunction "PD12_P$44") (pintype "bidirectional"))
    )
    (net (code "122") (name "unconnected-(U$2-PD13-PadP$45)") (class "Default")
      (node (ref "U$2") (pin "P$45") (pinfunction "PD13_P$45") (pintype "bidirectional"))
    )
    (net (code "123") (name "unconnected-(U$2-PD14-PadP$46)") (class "Default")
      (node (ref "U$2") (pin "P$46") (pinfunction "PD14_P$46") (pintype "bidirectional"))
    )
    (net (code "124") (name "unconnected-(U$2-PD15-PadP$47)") (class "Default")
      (node (ref "U$2") (pin "P$47") (pinfunction "PD15_P$47") (pintype "bidirectional"))
    )
    (net (code "125") (name "unconnected-(U$2-PE0-PadP$67)") (class "Default")
      (node (ref "U$2") (pin "P$67") (pinfunction "PE0_P$67") (pintype "bidirectional"))
    )
    (net (code "126") (name "unconnected-(U$2-PE1-PadP$68)") (class "Default")
      (node (ref "U$2") (pin "P$68") (pinfunction "PE1_P$68") (pintype "bidirectional"))
    )
    (net (code "127") (name "unconnected-(U$2-PE2-PadP$65)") (class "Default")
      (node (ref "U$2") (pin "P$65") (pinfunction "PE2_P$65") (pintype "bidirectional"))
    )
    (net (code "128") (name "unconnected-(U$2-PE3-PadP$66)") (class "Default")
      (node (ref "U$2") (pin "P$66") (pinfunction "PE3_P$66") (pintype "bidirectional"))
    )
    (net (code "129") (name "unconnected-(U$2-PE4-PadP$63)") (class "Default")
      (node (ref "U$2") (pin "P$63") (pinfunction "PE4_P$63") (pintype "bidirectional"))
    )
    (net (code "130") (name "unconnected-(U$2-PE5-PadP$64)") (class "Default")
      (node (ref "U$2") (pin "P$64") (pinfunction "PE5_P$64") (pintype "bidirectional"))
    )
    (net (code "131") (name "unconnected-(U$2-PE6-PadP$61)") (class "Default")
      (node (ref "U$2") (pin "P$61") (pinfunction "PE6_P$61") (pintype "bidirectional"))
    )
    (net (code "132") (name "unconnected-(U$2-PE7-PadP$25)") (class "Default")
      (node (ref "U$2") (pin "P$25") (pinfunction "PE7_P$25") (pintype "bidirectional"))
    )
    (net (code "133") (name "unconnected-(U$2-PE8-PadP$26)") (class "Default")
      (node (ref "U$2") (pin "P$26") (pinfunction "PE8_P$26") (pintype "bidirectional"))
    )
    (net (code "134") (name "unconnected-(U$2-PE9-PadP$27)") (class "Default")
      (node (ref "U$2") (pin "P$27") (pinfunction "PE9_P$27") (pintype "bidirectional"))
    )
    (net (code "135") (name "unconnected-(U$2-PE10-PadP$28)") (class "Default")
      (node (ref "U$2") (pin "P$28") (pinfunction "PE10_P$28") (pintype "bidirectional"))
    )
    (net (code "136") (name "unconnected-(U$2-PE11-PadP$29)") (class "Default")
      (node (ref "U$2") (pin "P$29") (pinfunction "PE11_P$29") (pintype "bidirectional"))
    )
    (net (code "137") (name "unconnected-(U$2-PE12-PadP$30)") (class "Default")
      (node (ref "U$2") (pin "P$30") (pinfunction "PE12_P$30") (pintype "bidirectional"))
    )
    (net (code "138") (name "unconnected-(U$2-PE13-PadP$31)") (class "Default")
      (node (ref "U$2") (pin "P$31") (pinfunction "PE13_P$31") (pintype "bidirectional"))
    )
    (net (code "139") (name "unconnected-(U$2-PE14-PadP$32)") (class "Default")
      (node (ref "U$2") (pin "P$32") (pinfunction "PE14_P$32") (pintype "bidirectional"))
    )
    (net (code "140") (name "unconnected-(U$2-PE15-PadP$33)") (class "Default")
      (node (ref "U$2") (pin "P$33") (pinfunction "PE15_P$33") (pintype "bidirectional"))
    )
    (net (code "141") (name "unconnected-(U$2-PH0-PadP$57)") (class "Default")
      (node (ref "U$2") (pin "P$57") (pinfunction "PH0_P$57") (pintype "bidirectional"))
    )
    (net (code "142") (name "unconnected-(U$2-PH1-PadP$58)") (class "Default")
      (node (ref "U$2") (pin "P$58") (pinfunction "PH1_P$58") (pintype "bidirectional"))
    )
    (net (code "143") (name "unconnected-(U$2-VDD-PadP$3)") (class "Default")
      (node (ref "U$2") (pin "P$3") (pinfunction "VDD_P$3") (pintype "bidirectional"))
    )
    (net (code "144") (name "unconnected-(U$2-VDD1-PadP$4)") (class "Default")
      (node (ref "U$2") (pin "P$4") (pinfunction "VDD1_P$4") (pintype "bidirectional"))
    )
    (net (code "145") (name "unconnected-(U$2-VDD2-PadP$55)") (class "Default")
      (node (ref "U$2") (pin "P$55") (pinfunction "VDD2_P$55") (pintype "bidirectional"))
    )
    (net (code "146") (name "unconnected-(U$2-VDD3-PadP$56)") (class "Default")
      (node (ref "U$2") (pin "P$56") (pinfunction "VDD3_P$56") (pintype "bidirectional"))
    )
    (net (code "147") (name "unconnected-(U$2-VDD4-PadP$72)") (class "Default")
      (node (ref "U$2") (pin "P$72") (pinfunction "VDD4_P$72") (pintype "bidirectional"))
    )
  )
)
